# V0p2_Main_PCB2.net
KiCad netlist of a schematic drawn in EAGLE
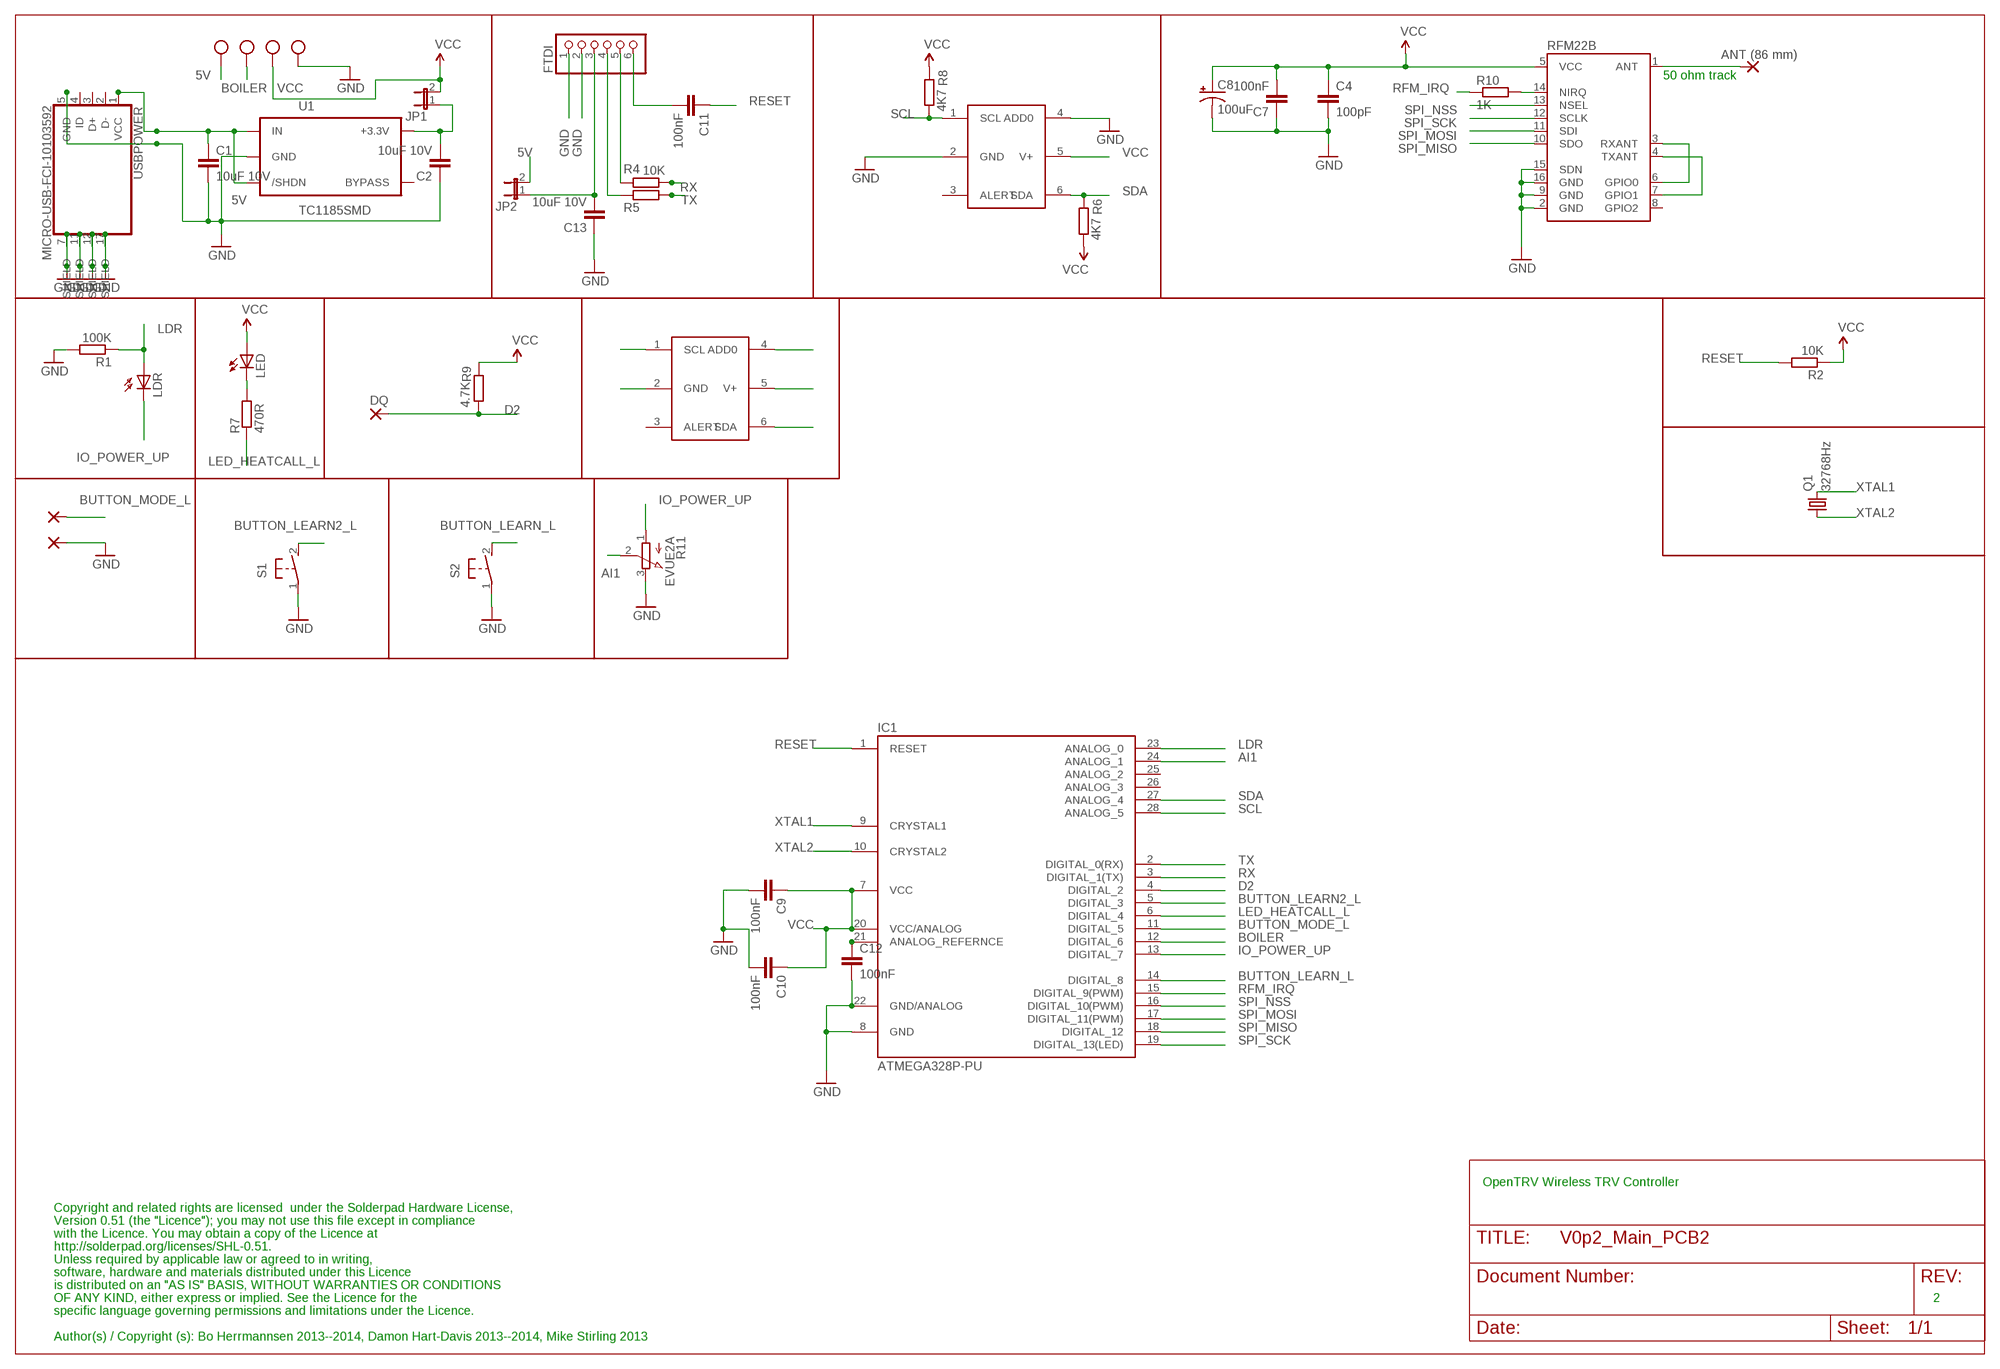
[diagram p0: schematic, sheet 1]

(export (version "E")
  (design (tool "Eeschema 10.0.6"))
  (components
    (comp (ref "ANT")
      (value "ANT (86 mm)")
      (footprint "eagle-import:2,15_1,0")
      (libsource (lib "eagle-import") (part "2,15/1,0"))
    )
    (comp (ref "C1")
      (value "10uF 10V")
      (footprint "eagle-import:0603-CAP")
      (libsource (lib "eagle-import") (part "CAP0603-CAP"))
    )
    (comp (ref "C2")
      (value "10uF 10V")
      (footprint "eagle-import:0603-CAP")
      (libsource (lib "eagle-import") (part "CAP0603-CAP"))
    )
    (comp (ref "C4")
      (value "100pF")
      (footprint "eagle-import:0603-CAP")
      (libsource (lib "eagle-import") (part "CAP0603-CAP"))
    )
    (comp (ref "C7")
      (value "100nF")
      (footprint "eagle-import:0603-CAP")
      (libsource (lib "eagle-import") (part "CAP0603-CAP"))
    )
    (comp (ref "C8")
      (value "100uF")
      (footprint "eagle-import:EIA3216")
      (libsource (lib "eagle-import") (part "CAP_POL1206"))
    )
    (comp (ref "C9")
      (value "100nF")
      (footprint "eagle-import:0603-CAP")
      (libsource (lib "eagle-import") (part "CAP0603-CAP"))
    )
    (comp (ref "C10")
      (value "100nF")
      (footprint "eagle-import:0603-CAP")
      (libsource (lib "eagle-import") (part "CAP0603-CAP"))
    )
    (comp (ref "C11")
      (value "100nF")
      (footprint "eagle-import:0603-CAP")
      (libsource (lib "eagle-import") (part "CAP0603-CAP"))
    )
    (comp (ref "C12")
      (value "100nF")
      (footprint "eagle-import:0603-CAP")
      (libsource (lib "eagle-import") (part "CAP0603-CAP"))
    )
    (comp (ref "C13")
      (value "10uF 10V")
      (footprint "eagle-import:0603-CAP")
      (libsource (lib "eagle-import") (part "CAP0603-CAP"))
    )
    (comp (ref "DQ")
      (value "2,15/1,0")
      (footprint "eagle-import:2,15_1,0")
      (libsource (lib "eagle-import") (part "2,15/1,0"))
    )
    (comp (ref "FTDI")
      (value "PINHD-1X6/90")
      (footprint "eagle-import:1X06_90")
      (libsource (lib "eagle-import") (part "PINHD-1X6/90"))
    )
    (comp (ref "IC1")
      (value "ATMEGA328P-PU")
      (footprint "eagle-import:DIL28-3")
      (libsource (lib "eagle-import") (part "ATMEGA8-PU"))
    )
    (comp (ref "JP1")
      (value "JP1E")
      (footprint "eagle-import:JP1")
      (libsource (lib "eagle-import") (part "JP1E"))
    )
    (comp (ref "JP2")
      (value "JP1E")
      (footprint "eagle-import:JP1")
      (libsource (lib "eagle-import") (part "JP1E"))
    )
    (comp (ref "LDR")
      (value "BPX65")
      (footprint "eagle-import:BPX65")
      (fields (field (name "MPN") "BPX65."))
      (libsource (lib "eagle-import") (part "BPX65"))
    )
    (comp (ref "LED")
      (value "LED3MM")
      (footprint "eagle-import:LED3MM")
      (libsource (lib "eagle-import") (part "LED3MM"))
    )
    (comp (ref "MODE")
      (value "2,15/1,0")
      (footprint "eagle-import:2,15_1,0")
      (libsource (lib "eagle-import") (part "2,15/1,0"))
    )
    (comp (ref "MODE1")
      (value "2,15/1,0")
      (footprint "eagle-import:2,15_1,0")
      (libsource (lib "eagle-import") (part "2,15/1,0"))
    )
    (comp (ref "Q1")
      (value "32768Hz")
      (footprint "eagle-import:MC-306")
      (fields (field (name "MPN") "MC-306 60.0KHZ  100PPM ,12.5PF"))
      (libsource (lib "eagle-import") (part "MC-306"))
    )
    (comp (ref "R1")
      (value "100K")
      (footprint "eagle-import:R0603")
      (libsource (lib "eagle-import") (part "R-EU_R0603"))
    )
    (comp (ref "R2")
      (value "10K")
      (footprint "eagle-import:R0603")
      (libsource (lib "eagle-import") (part "R-EU_R0603"))
    )
    (comp (ref "R4")
      (value "10K")
      (footprint "eagle-import:R0603")
      (libsource (lib "eagle-import") (part "R-EU_R0603"))
    )
    (comp (ref "R5")
      (value "10K")
      (footprint "eagle-import:R0603")
      (libsource (lib "eagle-import") (part "R-EU_R0603"))
    )
    (comp (ref "R6")
      (value "4K7")
      (footprint "eagle-import:R0603")
      (libsource (lib "eagle-import") (part "R-EU_R0603"))
    )
    (comp (ref "R7")
      (value "470R")
      (footprint "eagle-import:R0603")
      (libsource (lib "eagle-import") (part "R-EU_R0603"))
    )
    (comp (ref "R8")
      (value "4K7")
      (footprint "eagle-import:R0603")
      (libsource (lib "eagle-import") (part "R-EU_R0603"))
    )
    (comp (ref "R9")
      (value "4.7K")
      (footprint "eagle-import:R0603")
      (libsource (lib "eagle-import") (part "R-EU_R0603"))
    )
    (comp (ref "R10")
      (value "1K")
      (footprint "eagle-import:R0603")
      (libsource (lib "eagle-import") (part "R-EU_R0603"))
    )
    (comp (ref "R11")
      (value "EVUE2A")
      (footprint "eagle-import:EVUE")
      (libsource (lib "eagle-import") (part "EVUE2A"))
    )
    (comp (ref "RFM22B")
      (value "RFM22SMD")
      (footprint "eagle-import:RFM22-XXX-S2")
      (libsource (lib "eagle-import") (part "RFM22SMD"))
    )
    (comp (ref "S1")
      (value "31-XX")
      (footprint "eagle-import:B3F-31XX")
      (libsource (lib "eagle-import") (part "31-XX"))
    )
    (comp (ref "S2")
      (value "31-XX")
      (footprint "eagle-import:B3F-31XX")
      (libsource (lib "eagle-import") (part "31-XX"))
    )
    (comp (ref "TMP")
      (value "TMP112")
      (footprint "eagle-import:TMP112")
      (libsource (lib "eagle-import") (part "TMP112"))
    )
    (comp (ref "U$3")
      (value "TMP")
      (footprint "eagle-import:TMP112")
      (libsource (lib "eagle-import") (part "TMP112_2_TMP112"))
    )
    (comp (ref "U1")
      (value "TC1185SMD")
      (footprint "eagle-import:TC1185")
      (libsource (lib "eagle-import") (part "TC1185SMD"))
    )
    (comp (ref "USBPOWER")
      (value "MICRO-USB-FCI-10103592")
      (footprint "eagle-import:MICRO-USB-FCI-10103592")
      (libsource (lib "eagle-import") (part "MICRO-USB-FCI-10103592"))
    )
    (comp (ref "X1")
      (value "W237-102")
      (footprint "eagle-import:SCREWTERMINAL")
      (fields (field (name "MPN") "237-102"))
      (libsource (lib "eagle-import") (part "W237-102"))
    )
    (comp (ref "X2")
      (value "W237-102")
      (footprint "eagle-import:SCREWTERMINAL")
      (fields (field (name "MPN") "237-102"))
      (libsource (lib "eagle-import") (part "W237-102"))
    )
  )
  (nets
    (net (code "1") (name "/5V") (class "Default")
      (node (ref "C1") (pin "1") (pinfunction "1_1") (pintype "passive"))
      (node (ref "JP2") (pin "2") (pinfunction "2_2") (pintype "passive"))
      (node (ref "U1") (pin "1") (pinfunction "IN_1") (pintype "passive"))
      (node (ref "U1") (pin "3") (pinfunction "/SHDN_3") (pintype "passive"))
      (node (ref "USBPOWER") (pin "1") (pinfunction "VCC_1") (pintype "bidirectional"))
      (node (ref "X1") (pin "2") (pinfunction "KL_2") (pintype "passive"))
    )
    (net (code "2") (name "/AI1") (class "Default")
      (node (ref "IC1") (pin "24") (pinfunction "ANALOG_1_24") (pintype "bidirectional"))
      (node (ref "R11") (pin "2") (pinfunction "S_2") (pintype "passive"))
    )
    (net (code "3") (name "/BOILER") (class "Default")
      (node (ref "IC1") (pin "12") (pinfunction "DIGITAL_6_12") (pintype "bidirectional"))
      (node (ref "X1") (pin "1") (pinfunction "KL_1") (pintype "passive"))
    )
    (net (code "4") (name "/BUTTON_LEARN2_L") (class "Default")
      (node (ref "IC1") (pin "5") (pinfunction "DIGITAL_3_5") (pintype "bidirectional"))
      (node (ref "S1") (pin "2") (pinfunction "S_2") (pintype "passive"))
    )
    (net (code "5") (name "/BUTTON_LEARN_L") (class "Default")
      (node (ref "IC1") (pin "14") (pinfunction "DIGITAL_8_14") (pintype "bidirectional"))
      (node (ref "S2") (pin "2") (pinfunction "S_2") (pintype "passive"))
    )
    (net (code "6") (name "/BUTTON_MODE_L") (class "Default")
      (node (ref "IC1") (pin "11") (pinfunction "DIGITAL_5_11") (pintype "bidirectional"))
      (node (ref "MODE1") (pin "1") (pinfunction "P_1") (pintype "passive"))
    )
    (net (code "7") (name "/D2") (class "Default")
      (node (ref "DQ") (pin "1") (pinfunction "P_1") (pintype "passive"))
      (node (ref "IC1") (pin "4") (pinfunction "DIGITAL_2_4") (pintype "bidirectional"))
      (node (ref "R9") (pin "1") (pinfunction "1_1") (pintype "passive"))
    )
    (net (code "8") (name "/IO_POWER_UP") (class "Default")
      (node (ref "IC1") (pin "13") (pinfunction "DIGITAL_7_13") (pintype "bidirectional"))
      (node (ref "LDR") (pin "K") (pinfunction "C_K") (pintype "passive"))
      (node (ref "R11") (pin "1") (pinfunction "A_1") (pintype "passive"))
    )
    (net (code "9") (name "/LDR") (class "Default")
      (node (ref "IC1") (pin "23") (pinfunction "ANALOG_0_23") (pintype "bidirectional"))
      (node (ref "LDR") (pin "A") (pinfunction "A_A") (pintype "passive"))
      (node (ref "R1") (pin "1") (pinfunction "1_1") (pintype "passive"))
    )
    (net (code "10") (name "/LED_HEATCALL_L") (class "Default")
      (node (ref "IC1") (pin "6") (pinfunction "DIGITAL_4_6") (pintype "bidirectional"))
      (node (ref "R7") (pin "1") (pinfunction "1_1") (pintype "passive"))
    )
    (net (code "11") (name "/RESET") (class "Default")
      (node (ref "C11") (pin "1") (pinfunction "1_1") (pintype "passive"))
      (node (ref "IC1") (pin "1") (pinfunction "RESET_1") (pintype "bidirectional"))
      (node (ref "R2") (pin "2") (pinfunction "2_2") (pintype "passive"))
    )
    (net (code "12") (name "/RFM_IRQ") (class "Default")
      (node (ref "IC1") (pin "15") (pinfunction "DIGITAL_9(PWM)_15") (pintype "bidirectional"))
      (node (ref "R10") (pin "1") (pinfunction "1_1") (pintype "passive"))
    )
    (net (code "13") (name "/RX") (class "Default")
      (node (ref "IC1") (pin "3") (pinfunction "DIGITAL_1(TX)_3") (pintype "bidirectional"))
      (node (ref "R4") (pin "1") (pinfunction "1_1") (pintype "passive"))
    )
    (net (code "14") (name "/SCL") (class "Default")
      (node (ref "IC1") (pin "28") (pinfunction "ANALOG_5_28") (pintype "bidirectional"))
      (node (ref "R8") (pin "1") (pinfunction "1_1") (pintype "passive"))
      (node (ref "TMP") (pin "1") (pinfunction "SCL_1") (pintype "bidirectional"))
      (node (ref "U$3") (pin "1") (pinfunction "SCL_1") (pintype "bidirectional"))
    )
    (net (code "15") (name "/SDA") (class "Default")
      (node (ref "IC1") (pin "27") (pinfunction "ANALOG_4_27") (pintype "bidirectional"))
      (node (ref "R6") (pin "2") (pinfunction "2_2") (pintype "passive"))
      (node (ref "TMP") (pin "6") (pinfunction "SDA_6") (pintype "bidirectional"))
      (node (ref "U$3") (pin "6") (pinfunction "SDA_6") (pintype "bidirectional"))
    )
    (net (code "16") (name "/SPI_MISO") (class "Default")
      (node (ref "IC1") (pin "18") (pinfunction "DIGITAL_12_18") (pintype "bidirectional"))
      (node (ref "RFM22B") (pin "10") (pinfunction "SDO_10") (pintype "output"))
    )
    (net (code "17") (name "/SPI_MOSI") (class "Default")
      (node (ref "IC1") (pin "17") (pinfunction "DIGITAL_11(PWM)_17") (pintype "bidirectional"))
      (node (ref "RFM22B") (pin "11") (pinfunction "SDI_11") (pintype "input"))
    )
    (net (code "18") (name "/SPI_NSS") (class "Default")
      (node (ref "IC1") (pin "16") (pinfunction "DIGITAL_10(PWM)_16") (pintype "bidirectional"))
      (node (ref "RFM22B") (pin "13") (pinfunction "NSEL_13") (pintype "input"))
    )
    (net (code "19") (name "/SPI_SCK") (class "Default")
      (node (ref "IC1") (pin "19") (pinfunction "DIGITAL_13(LED)_19") (pintype "bidirectional"))
      (node (ref "RFM22B") (pin "12") (pinfunction "SCLK_12") (pintype "input"))
    )
    (net (code "20") (name "/TX") (class "Default")
      (node (ref "IC1") (pin "2") (pinfunction "DIGITAL_0(RX)_2") (pintype "bidirectional"))
      (node (ref "R5") (pin "1") (pinfunction "1_1") (pintype "passive"))
    )
    (net (code "21") (name "/XTAL1") (class "Default")
      (node (ref "IC1") (pin "9") (pinfunction "CRYSTAL1_9") (pintype "bidirectional"))
      (node (ref "Q1") (pin "4") (pinfunction "2_4") (pintype "passive"))
    )
    (net (code "22") (name "/XTAL2") (class "Default")
      (node (ref "IC1") (pin "10") (pinfunction "CRYSTAL2_10") (pintype "bidirectional"))
      (node (ref "Q1") (pin "1") (pinfunction "1_1") (pintype "passive"))
    )
    (net (code "23") (name "GND") (class "Default")
      (node (ref "C1") (pin "2") (pinfunction "2_2") (pintype "passive"))
      (node (ref "C10") (pin "2") (pinfunction "2_2") (pintype "passive"))
      (node (ref "C12") (pin "2") (pinfunction "2_2") (pintype "passive"))
      (node (ref "C13") (pin "1") (pinfunction "1_1") (pintype "passive"))
      (node (ref "C2") (pin "1") (pinfunction "1_1") (pintype "passive"))
      (node (ref "C4") (pin "2") (pinfunction "2_2") (pintype "passive"))
      (node (ref "C7") (pin "1") (pinfunction "1_1") (pintype "passive"))
      (node (ref "C8") (pin "C") (pinfunction "-_C") (pintype "passive"))
      (node (ref "C9") (pin "2") (pinfunction "2_2") (pintype "passive"))
      (node (ref "FTDI") (pin "1") (pinfunction "1_1") (pintype "passive"))
      (node (ref "FTDI") (pin "2") (pinfunction "2_2") (pintype "passive"))
      (node (ref "IC1") (pin "22") (pinfunction "GND/ANALOG_22") (pintype "power_in"))
      (node (ref "IC1") (pin "8") (pinfunction "GND_8") (pintype "power_in"))
      (node (ref "MODE") (pin "1") (pinfunction "P_1") (pintype "passive"))
      (node (ref "R1") (pin "2") (pinfunction "2_2") (pintype "passive"))
      (node (ref "R11") (pin "3") (pinfunction "E_3") (pintype "passive"))
      (node (ref "RFM22B") (pin "15") (pinfunction "SDN_15") (pintype "input"))
      (node (ref "RFM22B") (pin "16") (pinfunction "GND_16") (pintype "power_in"))
      (node (ref "RFM22B") (pin "2") (pinfunction "GND_2") (pintype "power_in"))
      (node (ref "RFM22B") (pin "9") (pinfunction "GND_9") (pintype "power_in"))
      (node (ref "S1") (pin "1") (pinfunction "P_1") (pintype "passive"))
      (node (ref "S2") (pin "1") (pinfunction "P_1") (pintype "passive"))
      (node (ref "TMP") (pin "2") (pinfunction "GND_2") (pintype "bidirectional"))
      (node (ref "TMP") (pin "4") (pinfunction "ADD0_4") (pintype "bidirectional"))
      (node (ref "U$3") (pin "2") (pinfunction "GND_2") (pintype "bidirectional"))
      (node (ref "U$3") (pin "4") (pinfunction "ADD0_4") (pintype "bidirectional"))
      (node (ref "U1") (pin "2") (pinfunction "GND_2") (pintype "passive"))
      (node (ref "USBPOWER") (pin "11") (pinfunction "SHIELD_11") (pintype "bidirectional"))
      (node (ref "USBPOWER") (pin "12") (pinfunction "SHIELD_12") (pintype "bidirectional"))
      (node (ref "USBPOWER") (pin "17") (pinfunction "SHIELD_17") (pintype "bidirectional"))
      (node (ref "USBPOWER") (pin "5") (pinfunction "GND_5") (pintype "bidirectional"))
      (node (ref "USBPOWER") (pin "7") (pinfunction "SHIELD_7") (pintype "bidirectional"))
      (node (ref "X2") (pin "2") (pinfunction "KL_2") (pintype "passive"))
    )
    (net (code "24") (name "Net-(ANT-P)") (class "Default")
      (node (ref "ANT") (pin "1") (pinfunction "P_1") (pintype "passive"))
      (node (ref "RFM22B") (pin "1") (pinfunction "ANT_1") (pintype "bidirectional"))
    )
    (net (code "25") (name "Net-(C11-Pad2)") (class "Default")
      (node (ref "C11") (pin "2") (pinfunction "2_2") (pintype "passive"))
      (node (ref "FTDI") (pin "6") (pinfunction "6_6") (pintype "passive"))
    )
    (net (code "26") (name "Net-(C13-Pad2)") (class "Default")
      (node (ref "C13") (pin "2") (pinfunction "2_2") (pintype "passive"))
      (node (ref "FTDI") (pin "3") (pinfunction "3_3") (pintype "passive"))
      (node (ref "JP2") (pin "1") (pinfunction "1_1") (pintype "passive"))
    )
    (net (code "27") (name "Net-(FTDI-Pad4)") (class "Default")
      (node (ref "FTDI") (pin "4") (pinfunction "4_4") (pintype "passive"))
      (node (ref "R5") (pin "2") (pinfunction "2_2") (pintype "passive"))
    )
    (net (code "28") (name "Net-(FTDI-Pad5)") (class "Default")
      (node (ref "FTDI") (pin "5") (pinfunction "5_5") (pintype "passive"))
      (node (ref "R4") (pin "2") (pinfunction "2_2") (pintype "passive"))
    )
    (net (code "29") (name "Net-(IC1-ANALOG_REFERNCE)") (class "Default")
      (node (ref "C12") (pin "1") (pinfunction "1_1") (pintype "passive"))
      (node (ref "IC1") (pin "21") (pinfunction "ANALOG_REFERNCE_21") (pintype "passive"))
    )
    (net (code "30") (name "Net-(LED-C)") (class "Default")
      (node (ref "LED") (pin "K") (pinfunction "C_K") (pintype "passive"))
      (node (ref "R7") (pin "2") (pinfunction "2_2") (pintype "passive"))
    )
    (net (code "31") (name "Net-(RFM22B-GPIO0)") (class "Default")
      (node (ref "RFM22B") (pin "3") (pinfunction "RXANT_3") (pintype "input"))
      (node (ref "RFM22B") (pin "6") (pinfunction "GPIO0_6") (pintype "bidirectional"))
    )
    (net (code "32") (name "Net-(RFM22B-GPIO1)") (class "Default")
      (node (ref "RFM22B") (pin "4") (pinfunction "TXANT_4") (pintype "input"))
      (node (ref "RFM22B") (pin "7") (pinfunction "GPIO1_7") (pintype "bidirectional"))
    )
    (net (code "33") (name "Net-(RFM22B-NIRQ)") (class "Default")
      (node (ref "R10") (pin "2") (pinfunction "2_2") (pintype "passive"))
      (node (ref "RFM22B") (pin "14") (pinfunction "NIRQ_14") (pintype "output"))
    )
    (net (code "34") (name "Net-(U1-+3.3V)") (class "Default")
      (node (ref "C2") (pin "2") (pinfunction "2_2") (pintype "passive"))
      (node (ref "JP1") (pin "1") (pinfunction "1_1") (pintype "passive"))
      (node (ref "U1") (pin "5") (pinfunction "+3.3V_5") (pintype "power_in"))
    )
    (net (code "35") (name "VCC") (class "Default")
      (node (ref "C10") (pin "1") (pinfunction "1_1") (pintype "passive"))
      (node (ref "C4") (pin "1") (pinfunction "1_1") (pintype "passive"))
      (node (ref "C7") (pin "2") (pinfunction "2_2") (pintype "passive"))
      (node (ref "C8") (pin "A") (pinfunction "+_A") (pintype "passive"))
      (node (ref "C9") (pin "1") (pinfunction "1_1") (pintype "passive"))
      (node (ref "IC1") (pin "20") (pinfunction "VCC/ANALOG_20") (pintype "passive"))
      (node (ref "IC1") (pin "7") (pinfunction "VCC_7") (pintype "power_in"))
      (node (ref "JP1") (pin "2") (pinfunction "2_2") (pintype "passive"))
      (node (ref "LED") (pin "A") (pinfunction "A_A") (pintype "passive"))
      (node (ref "R2") (pin "1") (pinfunction "1_1") (pintype "passive"))
      (node (ref "R6") (pin "1") (pinfunction "1_1") (pintype "passive"))
      (node (ref "R8") (pin "2") (pinfunction "2_2") (pintype "passive"))
      (node (ref "R9") (pin "2") (pinfunction "2_2") (pintype "passive"))
      (node (ref "RFM22B") (pin "5") (pinfunction "VCC_5") (pintype "bidirectional"))
      (node (ref "TMP") (pin "5") (pinfunction "V+_5") (pintype "bidirectional"))
      (node (ref "U$3") (pin "5") (pinfunction "V+_5") (pintype "bidirectional"))
      (node (ref "X2") (pin "1") (pinfunction "KL_1") (pintype "passive"))
    )
    (net (code "36") (name "unconnected-(IC1-ANALOG_2-Pad25)") (class "Default")
      (node (ref "IC1") (pin "25") (pinfunction "ANALOG_2_25") (pintype "bidirectional"))
    )
    (net (code "37") (name "unconnected-(IC1-ANALOG_3-Pad26)") (class "Default")
      (node (ref "IC1") (pin "26") (pinfunction "ANALOG_3_26") (pintype "bidirectional"))
    )
    (net (code "38") (name "unconnected-(RFM22B-GPIO2-Pad8)") (class "Default")
      (node (ref "RFM22B") (pin "8") (pinfunction "GPIO2_8") (pintype "bidirectional"))
    )
    (net (code "39") (name "unconnected-(TMP-ALERT-Pad3)") (class "Default")
      (node (ref "TMP") (pin "3") (pinfunction "ALERT_3") (pintype "bidirectional"))
    )
    (net (code "40") (name "unconnected-(U$3-ALERT-Pad3)") (class "Default")
      (node (ref "U$3") (pin "3") (pinfunction "ALERT_3") (pintype "bidirectional"))
    )
    (net (code "41") (name "unconnected-(U1-BYPASS-Pad4)") (class "Default")
      (node (ref "U1") (pin "4") (pinfunction "BYPASS_4") (pintype "passive"))
    )
    (net (code "42") (name "unconnected-(USBPOWER-D+-Pad3)") (class "Default")
      (node (ref "USBPOWER") (pin "3") (pinfunction "D+_3") (pintype "bidirectional"))
    )
    (net (code "43") (name "unconnected-(USBPOWER-D--Pad2)") (class "Default")
      (node (ref "USBPOWER") (pin "2") (pinfunction "D-_2") (pintype "bidirectional"))
    )
    (net (code "44") (name "unconnected-(USBPOWER-ID-Pad4)") (class "Default")
      (node (ref "USBPOWER") (pin "4") (pinfunction "ID_4") (pintype "bidirectional"))
    )
  )
)
